# Ethernet_PHY_RJ45.net
KiCad netlist of a schematic drawn in Altium Designer
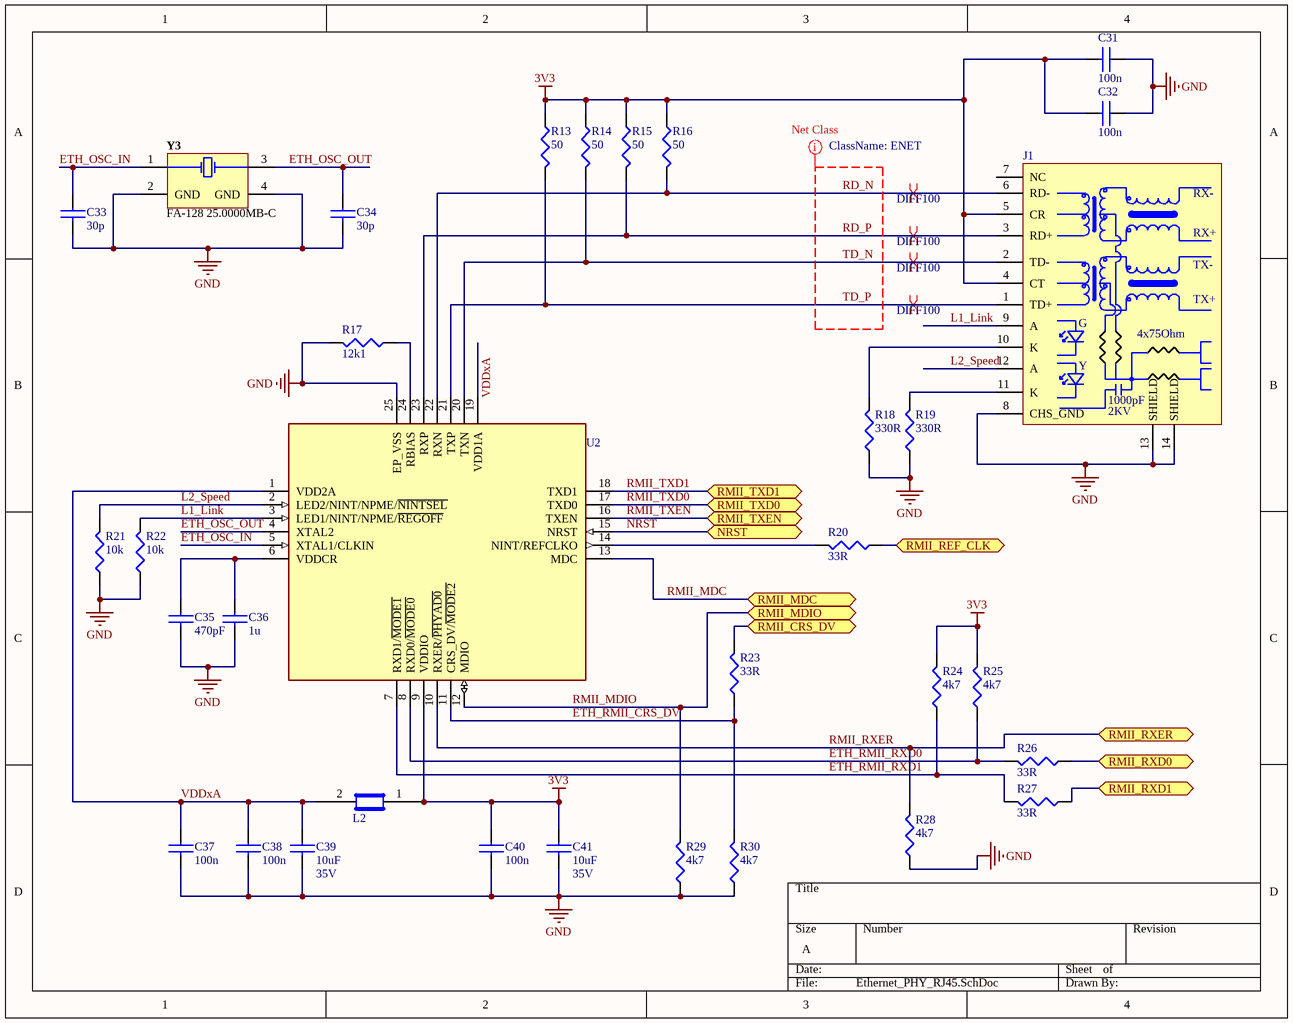
[diagram p0: Ethernet_PHY_RJ45.SchDoc]

(export (version "E")
  (design (tool "Eeschema 10.0.6"))
  (components
    (comp (ref "C31")
      (value "100n")
      (footprint "C0402")
      (description "CAP CER .10UF 50V X5R 10% 0402")
      (fields
        (field (name "MANUFACTURER") "TDK Corporation")
        (field (name "MANUFACTURER PART NUMBER") "C1005X5R1H104K")
      )
      (libsource (lib "iMX6_Rex_Development_Baseboard_V1I1") (part "C1005X5R1H104K"))
    )
    (comp (ref "C32")
      (value "100n")
      (footprint "C0402")
      (description "CAP CER .10UF 50V X5R 10% 0402")
      (fields
        (field (name "MANUFACTURER") "TDK Corporation")
        (field (name "MANUFACTURER PART NUMBER") "C1005X5R1H104K")
      )
      (libsource (lib "iMX6_Rex_Development_Baseboard_V1I1") (part "C1005X5R1H104K"))
    )
    (comp (ref "C33")
      (value "30p")
      (footprint "C0402")
      (description "CAP CER 18PF 50V C0G 5% 0402")
      (fields
        (field (name "MANUFACTURER") "TDK Corporation")
        (field (name "MANUFACTURER PART NUMBER") "C1005C0G1H180J")
      )
      (libsource (lib "iMX6_Rex_Development_Baseboard_V1I1") (part "C1005C0G1H180J"))
    )
    (comp (ref "C34")
      (value "30p")
      (footprint "C0402")
      (description "CAP CER 18PF 50V C0G 5% 0402")
      (fields
        (field (name "MANUFACTURER") "TDK Corporation")
        (field (name "MANUFACTURER PART NUMBER") "C1005C0G1H180J")
      )
      (libsource (lib "iMX6_Rex_Development_Baseboard_V1I1") (part "C1005C0G1H180J"))
    )
    (comp (ref "C35")
      (value "470pF")
      (footprint "C0402")
      (description "CAP CER 270PF 50V 10% X7R 0402")
      (fields
        (field (name "MANUFACTURER") "Murata Electronics North America")
        (field (name "MANUFACTURER PART NUMBER") "GRM155R71H271KA01D")
        (field (name ".CHECKED PCB") "RF")
        (field (name ".CHECKED SCH") "RF")
      )
      (libsource (lib "iMX6_Rex_Development_Baseboard_V1I1") (part "GRM155R71H271KA01D"))
    )
    (comp (ref "C36")
      (value "1u")
      (footprint "C0402")
      (description "CAP CER 1.0UF 16V X5R 0402")
      (fields
        (field (name "MANUFACTURER") "TDK Corporation")
        (field (name "MANUFACTURER PART NUMBER") "C1005X5R1C105K")
      )
      (libsource (lib "iMX6_Rex_Development_Baseboard_V1I1") (part "C1005X5R1C105K"))
    )
    (comp (ref "C37")
      (value "100n")
      (footprint "C0402")
      (description "CAP CER .10UF 50V X5R 10% 0402")
      (fields
        (field (name "MANUFACTURER") "TDK Corporation")
        (field (name "MANUFACTURER PART NUMBER") "C1005X5R1H104K")
      )
      (libsource (lib "iMX6_Rex_Development_Baseboard_V1I1") (part "C1005X5R1H104K"))
    )
    (comp (ref "C38")
      (value "100n")
      (footprint "C0402")
      (description "CAP CER .10UF 50V X5R 10% 0402")
      (fields
        (field (name "MANUFACTURER") "TDK Corporation")
        (field (name "MANUFACTURER PART NUMBER") "C1005X5R1H104K")
      )
      (libsource (lib "iMX6_Rex_Development_Baseboard_V1I1") (part "C1005X5R1H104K"))
    )
    (comp (ref "C39")
      (value "10uF")
      (footprint "C1206")
      (description "CAP CER 10UF 35V X5R 1206")
      (fields
        (field (name "MANUFACTURER") "Murata Electronics North America")
        (field (name "MANUFACTURER PART NUMBER") "GRM31CR6YA106KA12L")
        (field (name "VOLTAGE - RATED") "35V")
      )
      (libsource (lib "iMX6_Rex_Development_Baseboard_V1I1") (part "GRM31CR6YA106KA12L"))
    )
    (comp (ref "C40")
      (value "100n")
      (footprint "C0402")
      (description "CAP CER .10UF 50V X5R 10% 0402")
      (fields
        (field (name "MANUFACTURER") "TDK Corporation")
        (field (name "MANUFACTURER PART NUMBER") "C1005X5R1H104K")
      )
      (libsource (lib "iMX6_Rex_Development_Baseboard_V1I1") (part "C1005X5R1H104K"))
    )
    (comp (ref "C41")
      (value "10uF")
      (footprint "C1206")
      (description "CAP CER 10UF 35V X5R 1206")
      (fields
        (field (name "MANUFACTURER") "Murata Electronics North America")
        (field (name "MANUFACTURER PART NUMBER") "GRM31CR6YA106KA12L")
        (field (name "VOLTAGE - RATED") "35V")
      )
      (libsource (lib "iMX6_Rex_Development_Baseboard_V1I1") (part "GRM31CR6YA106KA12L"))
    )
    (comp (ref "J1")
      (value "RJ45")
      (footprint "RJ45_HAN_RUN")
      (description "DIP RJ45 Connector;")
      (fields (field (name "MANUFACTURER") "HanRun") (field (name "MANUFACTURER PART NUMBER") "HR911105A"))
      (libsource (lib "L1") (part "HR911105A"))
    )
    (comp (ref "L2")
      (value "MPZ1608S601A 600OHM/1A")
      (footprint "C0603")
      (description "FERRITE CHIP BEAD 600 OHM SMD 1A")
      (fields
        (field (name "MANUFACTURER") "TDK Corporation")
        (field (name "MANUFACTURER PART NUMBER") "MPZ1608S601A")
        (field (name ".CHECKED PCB") "RF")
        (field (name ".CHECKED SCH") "RF")
      )
      (libsource (lib "iMX6_Rex_Development_Baseboard_V1I1") (part "MPZ1608S601A"))
    )
    (comp (ref "R13")
      (value "50")
      (footprint "R0402")
      (description "RES 10.0K OHM 1/16W 1% 0402 SMD")
      (fields
        (field (name "MANUFACTURER") "Yageo")
        (field (name "MANUFACTURER PART NUMBER") "RC0402FR-0710KL")
      )
      (libsource (lib "iMX6_Rex_Development_Baseboard_V1I1") (part "RC0402FR-0710KL"))
    )
    (comp (ref "R14")
      (value "50")
      (footprint "R0402")
      (description "RES 10.0K OHM 1/16W 1% 0402 SMD")
      (fields
        (field (name "MANUFACTURER") "Yageo")
        (field (name "MANUFACTURER PART NUMBER") "RC0402FR-0710KL")
      )
      (libsource (lib "iMX6_Rex_Development_Baseboard_V1I1") (part "RC0402FR-0710KL"))
    )
    (comp (ref "R15")
      (value "50")
      (footprint "R0402")
      (description "RES 10.0K OHM 1/16W 1% 0402 SMD")
      (fields
        (field (name "MANUFACTURER") "Yageo")
        (field (name "MANUFACTURER PART NUMBER") "RC0402FR-0710KL")
      )
      (libsource (lib "iMX6_Rex_Development_Baseboard_V1I1") (part "RC0402FR-0710KL"))
    )
    (comp (ref "R16")
      (value "50")
      (footprint "R0402")
      (description "RES 10.0K OHM 1/16W 1% 0402 SMD")
      (fields
        (field (name "MANUFACTURER") "Yageo")
        (field (name "MANUFACTURER PART NUMBER") "RC0402FR-0710KL")
      )
      (libsource (lib "iMX6_Rex_Development_Baseboard_V1I1") (part "RC0402FR-0710KL"))
    )
    (comp (ref "R17")
      (value "12k1")
      (footprint "R0402")
      (description "RES 10.0K OHM 1/16W 1% 0402 SMD")
      (fields
        (field (name "MANUFACTURER") "Yageo")
        (field (name "MANUFACTURER PART NUMBER") "RC0402FR-0710KL")
      )
      (libsource (lib "iMX6_Rex_Development_Baseboard_V1I1") (part "RC0402FR-0710KL"))
    )
    (comp (ref "R18")
      (value "330R")
      (footprint "R0402")
      (description "RES 330 OHM 1/16W 1% 0402 SMD")
      (fields
        (field (name "MANUFACTURER") "Vishay Dale")
        (field (name "MANUFACTURER PART NUMBER") "CRCW0402330RFKED")
        (field (name ".CHECKED PCB") "RF")
        (field (name ".CHECKED SCH") "RF")
      )
      (libsource (lib "iMX6_Rex_Development_Baseboard_V1I1") (part "CRCW0402330RFKED"))
    )
    (comp (ref "R19")
      (value "330R")
      (footprint "R0402")
      (description "RES 330 OHM 1/16W 1% 0402 SMD")
      (fields
        (field (name "MANUFACTURER") "Vishay Dale")
        (field (name "MANUFACTURER PART NUMBER") "CRCW0402330RFKED")
        (field (name ".CHECKED PCB") "RF")
        (field (name ".CHECKED SCH") "RF")
      )
      (libsource (lib "iMX6_Rex_Development_Baseboard_V1I1") (part "CRCW0402330RFKED"))
    )
    (comp (ref "R20")
      (value "33R")
      (footprint "R0402")
      (description "RES 330 OHM 1/16W 1% 0402 SMD")
      (fields
        (field (name "MANUFACTURER") "Vishay Dale")
        (field (name "MANUFACTURER PART NUMBER") "CRCW0402330RFKED")
        (field (name ".CHECKED PCB") "RF")
        (field (name ".CHECKED SCH") "RF")
      )
      (libsource (lib "iMX6_Rex_Development_Baseboard_V1I1") (part "CRCW0402330RFKED"))
    )
    (comp (ref "R21")
      (value "10k")
      (footprint "R0402")
      (description "RES 10.0K OHM 1/16W 1% 0402 SMD")
      (fields
        (field (name "MANUFACTURER") "Yageo")
        (field (name "MANUFACTURER PART NUMBER") "RC0402FR-0710KL")
      )
      (libsource (lib "iMX6_Rex_Development_Baseboard_V1I1") (part "RC0402FR-0710KL"))
    )
    (comp (ref "R22")
      (value "10k")
      (footprint "R0402")
      (description "RES 10.0K OHM 1/16W 1% 0402 SMD")
      (fields
        (field (name "MANUFACTURER") "Yageo")
        (field (name "MANUFACTURER PART NUMBER") "RC0402FR-0710KL")
      )
      (libsource (lib "iMX6_Rex_Development_Baseboard_V1I1") (part "RC0402FR-0710KL"))
    )
    (comp (ref "R23")
      (value "33R")
      (footprint "R0402")
      (description "RES 330 OHM 1/16W 1% 0402 SMD")
      (fields
        (field (name "MANUFACTURER") "Vishay Dale")
        (field (name "MANUFACTURER PART NUMBER") "CRCW0402330RFKED")
        (field (name ".CHECKED PCB") "RF")
        (field (name ".CHECKED SCH") "RF")
      )
      (libsource (lib "iMX6_Rex_Development_Baseboard_V1I1") (part "CRCW0402330RFKED"))
    )
    (comp (ref "R24")
      (value "4k7")
      (footprint "R0402")
      (description "RES 10.0K OHM 1/16W 1% 0402 SMD")
      (fields
        (field (name "MANUFACTURER") "Yageo")
        (field (name "MANUFACTURER PART NUMBER") "RC0402FR-0710KL")
      )
      (libsource (lib "iMX6_Rex_Development_Baseboard_V1I1") (part "RC0402FR-0710KL"))
    )
    (comp (ref "R25")
      (value "4k7")
      (footprint "R0402")
      (description "RES 10.0K OHM 1/16W 1% 0402 SMD")
      (fields
        (field (name "MANUFACTURER") "Yageo")
        (field (name "MANUFACTURER PART NUMBER") "RC0402FR-0710KL")
      )
      (libsource (lib "iMX6_Rex_Development_Baseboard_V1I1") (part "RC0402FR-0710KL"))
    )
    (comp (ref "R26")
      (value "33R")
      (footprint "R0402")
      (description "RES 330 OHM 1/16W 1% 0402 SMD")
      (fields
        (field (name "MANUFACTURER") "Vishay Dale")
        (field (name "MANUFACTURER PART NUMBER") "CRCW0402330RFKED")
        (field (name ".CHECKED PCB") "RF")
        (field (name ".CHECKED SCH") "RF")
      )
      (libsource (lib "iMX6_Rex_Development_Baseboard_V1I1") (part "CRCW0402330RFKED"))
    )
    (comp (ref "R27")
      (value "33R")
      (footprint "R0402")
      (description "RES 330 OHM 1/16W 1% 0402 SMD")
      (fields
        (field (name "MANUFACTURER") "Vishay Dale")
        (field (name "MANUFACTURER PART NUMBER") "CRCW0402330RFKED")
        (field (name ".CHECKED PCB") "RF")
        (field (name ".CHECKED SCH") "RF")
      )
      (libsource (lib "iMX6_Rex_Development_Baseboard_V1I1") (part "CRCW0402330RFKED"))
    )
    (comp (ref "R28")
      (value "4k7")
      (footprint "R0402")
      (description "RES 10.0K OHM 1/16W 1% 0402 SMD")
      (fields
        (field (name "MANUFACTURER") "Yageo")
        (field (name "MANUFACTURER PART NUMBER") "RC0402FR-0710KL")
      )
      (libsource (lib "iMX6_Rex_Development_Baseboard_V1I1") (part "RC0402FR-0710KL"))
    )
    (comp (ref "R29")
      (value "4k7")
      (footprint "R0402")
      (description "RES 10.0K OHM 1/16W 1% 0402 SMD")
      (fields
        (field (name "MANUFACTURER") "Yageo")
        (field (name "MANUFACTURER PART NUMBER") "RC0402FR-0710KL")
      )
      (libsource (lib "iMX6_Rex_Development_Baseboard_V1I1") (part "RC0402FR-0710KL"))
    )
    (comp (ref "R30")
      (value "4k7")
      (footprint "R0402")
      (description "RES 10.0K OHM 1/16W 1% 0402 SMD")
      (fields
        (field (name "MANUFACTURER") "Yageo")
        (field (name "MANUFACTURER PART NUMBER") "RC0402FR-0710KL")
      )
      (libsource (lib "iMX6_Rex_Development_Baseboard_V1I1") (part "RC0402FR-0710KL"))
    )
    (comp (ref "U2")
      (value "LAN8742A-CZ-TR")
      (footprint "SamacSys:QFN50P400X400X100-25N-D")
      (description "Integrated Circuit")
      (fields (field (name "MOUSER PART NUMBER") "579-LAN8742A-CZ-TR"))
      (libsource (lib "*") (part "LAN8742A-CZ-TR"))
    )
    (comp (ref "Y3")
      (value "FA-128 25.0000MB-C")
      (footprint "EPSON-FA-128_V")
      (description "Range Crystal Unit, 25 MHz, -40 to 85 degC, 4-Pin SMD, RoHS, Tape and Reel")
      (libsource (lib "MiniPC") (part "CMP-1695-00001-3"))
    )
  )
  (nets
    (net (code "1") (name "/ETH_OSC_IN") (class "Default")
      (node (ref "C33") (pin "1") (pinfunction "1_1") (pintype "passive"))
      (node (ref "U2") (pin "5") (pinfunction "XTAL1/CLKIN_5") (pintype "input"))
      (node (ref "Y3") (pin "1") (pinfunction "X1_1") (pintype "passive"))
    )
    (net (code "2") (name "/ETH_OSC_OUT") (class "Default")
      (node (ref "C34") (pin "1") (pinfunction "1_1") (pintype "passive"))
      (node (ref "U2") (pin "4") (pinfunction "XTAL2_4") (pintype "passive"))
      (node (ref "Y3") (pin "3") (pinfunction "X2_3") (pintype "passive"))
    )
    (net (code "3") (name "/ETH_RMII_CRS_DV") (class "Default")
      (node (ref "R23") (pin "1") (pinfunction "1_1") (pintype "passive"))
      (node (ref "R30") (pin "2") (pinfunction "2_2") (pintype "passive"))
      (node (ref "U2") (pin "11") (pinfunction "CRS_DV/~{MODE2}_11") (pintype "passive"))
    )
    (net (code "4") (name "/ETH_RMII_RXD0") (class "Default")
      (node (ref "R25") (pin "1") (pinfunction "1_1") (pintype "passive"))
      (node (ref "R26") (pin "2") (pinfunction "2_2") (pintype "passive"))
      (node (ref "U2") (pin "8") (pinfunction "RXD0/~{MODE0}_8") (pintype "passive"))
    )
    (net (code "5") (name "/ETH_RMII_RXD1") (class "Default")
      (node (ref "R24") (pin "1") (pinfunction "1_1") (pintype "passive"))
      (node (ref "R27") (pin "2") (pinfunction "2_2") (pintype "passive"))
      (node (ref "U2") (pin "7") (pinfunction "RXD1/~{MODE1}_7") (pintype "passive"))
    )
    (net (code "6") (name "/L1_Link") (class "Default")
      (node (ref "J1") (pin "9") (pinfunction "A_9") (pintype "power_in"))
      (node (ref "R22") (pin "2") (pinfunction "2_2") (pintype "passive"))
      (node (ref "U2") (pin "3") (pinfunction "LED1/NINT/NPME/~{REGOFF}_3") (pintype "input"))
    )
    (net (code "7") (name "/L2_Speed") (class "Default")
      (node (ref "J1") (pin "12") (pinfunction "A_12") (pintype "power_in"))
      (node (ref "R21") (pin "2") (pinfunction "2_2") (pintype "passive"))
      (node (ref "U2") (pin "2") (pinfunction "LED2/NINT/NPME/~{NINTSEL}_2") (pintype "input"))
    )
    (net (code "8") (name "/NRST") (class "Default")
      (node (ref "U2") (pin "15") (pinfunction "NRST_15") (pintype "input"))
    )
    (net (code "9") (name "/RD_N") (class "Default")
      (node (ref "J1") (pin "6") (pinfunction "RD-_6") (pintype "power_in"))
      (node (ref "R16") (pin "2") (pinfunction "2_2") (pintype "passive"))
      (node (ref "U2") (pin "22") (pinfunction "RXN_22") (pintype "passive"))
    )
    (net (code "10") (name "/RD_P") (class "Default")
      (node (ref "J1") (pin "3") (pinfunction "RD+_3") (pintype "power_in"))
      (node (ref "R15") (pin "2") (pinfunction "2_2") (pintype "passive"))
      (node (ref "U2") (pin "23") (pinfunction "RXP_23") (pintype "passive"))
    )
    (net (code "11") (name "/RMII_CRS_DV") (class "Default")
      (node (ref "R23") (pin "2") (pinfunction "2_2") (pintype "passive"))
    )
    (net (code "12") (name "/RMII_MDC") (class "Default")
      (node (ref "U2") (pin "13") (pinfunction "MDC_13") (pintype "passive"))
    )
    (net (code "13") (name "/RMII_MDIO") (class "Default")
      (node (ref "R29") (pin "2") (pinfunction "2_2") (pintype "passive"))
      (node (ref "U2") (pin "12") (pinfunction "MDIO_12") (pintype "bidirectional"))
    )
    (net (code "14") (name "/RMII_REF_CLK") (class "Default")
      (node (ref "R20") (pin "1") (pinfunction "1_1") (pintype "passive"))
    )
    (net (code "15") (name "/RMII_RXD0") (class "Default")
      (node (ref "R26") (pin "1") (pinfunction "1_1") (pintype "passive"))
    )
    (net (code "16") (name "/RMII_RXD1") (class "Default")
      (node (ref "R27") (pin "1") (pinfunction "1_1") (pintype "passive"))
    )
    (net (code "17") (name "/RMII_RXER") (class "Default")
      (node (ref "R28") (pin "2") (pinfunction "2_2") (pintype "passive"))
      (node (ref "U2") (pin "10") (pinfunction "RXER/~{PHYAD0}_10") (pintype "passive"))
    )
    (net (code "18") (name "/RMII_TXD0") (class "Default")
      (node (ref "U2") (pin "17") (pinfunction "TXD0_17") (pintype "passive"))
    )
    (net (code "19") (name "/RMII_TXD1") (class "Default")
      (node (ref "U2") (pin "18") (pinfunction "TXD1_18") (pintype "passive"))
    )
    (net (code "20") (name "/RMII_TXEN") (class "Default")
      (node (ref "U2") (pin "16") (pinfunction "TXEN_16") (pintype "passive"))
    )
    (net (code "21") (name "/TD_N") (class "Default")
      (node (ref "J1") (pin "2") (pinfunction "TD-_2") (pintype "power_in"))
      (node (ref "R14") (pin "2") (pinfunction "2_2") (pintype "passive"))
      (node (ref "U2") (pin "20") (pinfunction "TXN_20") (pintype "passive"))
    )
    (net (code "22") (name "/TD_P") (class "Default")
      (node (ref "J1") (pin "1") (pinfunction "TD+_1") (pintype "power_in"))
      (node (ref "R13") (pin "2") (pinfunction "2_2") (pintype "passive"))
      (node (ref "U2") (pin "21") (pinfunction "TXP_21") (pintype "passive"))
    )
    (net (code "23") (name "/VDDxA") (class "Default")
      (node (ref "C37") (pin "1") (pinfunction "1_1") (pintype "passive"))
      (node (ref "C38") (pin "1") (pinfunction "1_1") (pintype "passive"))
      (node (ref "C39") (pin "1") (pinfunction "1_1") (pintype "passive"))
      (node (ref "L2") (pin "2") (pinfunction "2_2") (pintype "passive"))
      (node (ref "U2") (pin "1") (pinfunction "VDD2A_1") (pintype "power_in"))
      (node (ref "U2") (pin "19") (pinfunction "VDD1A_19") (pintype "power_in"))
    )
    (net (code "24") (name "3V3") (class "Default")
      (node (ref "C31") (pin "2") (pinfunction "2_2") (pintype "passive"))
      (node (ref "C32") (pin "2") (pinfunction "2_2") (pintype "passive"))
      (node (ref "C40") (pin "1") (pinfunction "1_1") (pintype "passive"))
      (node (ref "C41") (pin "1") (pinfunction "1_1") (pintype "passive"))
      (node (ref "J1") (pin "4") (pinfunction "CT_4") (pintype "power_in"))
      (node (ref "J1") (pin "5") (pinfunction "CR_5") (pintype "power_in"))
      (node (ref "L2") (pin "1") (pinfunction "1_1") (pintype "passive"))
      (node (ref "R13") (pin "1") (pinfunction "1_1") (pintype "passive"))
      (node (ref "R14") (pin "1") (pinfunction "1_1") (pintype "passive"))
      (node (ref "R15") (pin "1") (pinfunction "1_1") (pintype "passive"))
      (node (ref "R16") (pin "1") (pinfunction "1_1") (pintype "passive"))
      (node (ref "R24") (pin "2") (pinfunction "2_2") (pintype "passive"))
      (node (ref "R25") (pin "2") (pinfunction "2_2") (pintype "passive"))
      (node (ref "U2") (pin "9") (pinfunction "VDDIO_9") (pintype "power_in"))
    )
    (net (code "25") (name "GND") (class "Default")
      (node (ref "C31") (pin "1") (pinfunction "1_1") (pintype "passive"))
      (node (ref "C32") (pin "1") (pinfunction "1_1") (pintype "passive"))
      (node (ref "C33") (pin "2") (pinfunction "2_2") (pintype "passive"))
      (node (ref "C34") (pin "2") (pinfunction "2_2") (pintype "passive"))
      (node (ref "C35") (pin "2") (pinfunction "2_2") (pintype "passive"))
      (node (ref "C36") (pin "2") (pinfunction "2_2") (pintype "passive"))
      (node (ref "C37") (pin "2") (pinfunction "2_2") (pintype "passive"))
      (node (ref "C38") (pin "2") (pinfunction "2_2") (pintype "passive"))
      (node (ref "C39") (pin "2") (pinfunction "2_2") (pintype "passive"))
      (node (ref "C40") (pin "2") (pinfunction "2_2") (pintype "passive"))
      (node (ref "C41") (pin "2") (pinfunction "2_2") (pintype "passive"))
      (node (ref "J1") (pin "13") (pinfunction "SHIELD_13") (pintype "power_in"))
      (node (ref "J1") (pin "14") (pinfunction "SHIELD_14") (pintype "power_in"))
      (node (ref "J1") (pin "8") (pinfunction "CHS_GND_8") (pintype "power_in"))
      (node (ref "R17") (pin "2") (pinfunction "2_2") (pintype "passive"))
      (node (ref "R18") (pin "1") (pinfunction "1_1") (pintype "passive"))
      (node (ref "R19") (pin "1") (pinfunction "1_1") (pintype "passive"))
      (node (ref "R21") (pin "1") (pinfunction "1_1") (pintype "passive"))
      (node (ref "R22") (pin "1") (pinfunction "1_1") (pintype "passive"))
      (node (ref "R28") (pin "1") (pinfunction "1_1") (pintype "passive"))
      (node (ref "R29") (pin "1") (pinfunction "1_1") (pintype "passive"))
      (node (ref "R30") (pin "1") (pinfunction "1_1") (pintype "passive"))
      (node (ref "U2") (pin "25") (pinfunction "EP_VSS_25") (pintype "power_in"))
      (node (ref "Y3") (pin "2") (pinfunction "GND_2") (pintype "power_in"))
      (node (ref "Y3") (pin "4") (pinfunction "GND_4") (pintype "power_in"))
    )
    (net (code "26") (name "Net-(J1-K-Pad10)") (class "Default")
      (node (ref "J1") (pin "10") (pinfunction "K_10") (pintype "power_in"))
      (node (ref "R18") (pin "2") (pinfunction "2_2") (pintype "passive"))
    )
    (net (code "27") (name "Net-(J1-K-Pad11)") (class "Default")
      (node (ref "J1") (pin "11") (pinfunction "K_11") (pintype "power_in"))
      (node (ref "R19") (pin "2") (pinfunction "2_2") (pintype "passive"))
    )
    (net (code "28") (name "Net-(U2-NINT{slash}REFCLKO)") (class "Default")
      (node (ref "R20") (pin "2") (pinfunction "2_2") (pintype "passive"))
      (node (ref "U2") (pin "14") (pinfunction "NINT/REFCLKO_14") (pintype "output"))
    )
    (net (code "29") (name "Net-(U2-RBIAS)") (class "Default")
      (node (ref "R17") (pin "1") (pinfunction "1_1") (pintype "passive"))
      (node (ref "U2") (pin "24") (pinfunction "RBIAS_24") (pintype "passive"))
    )
    (net (code "30") (name "Net-(U2-VDDCR)") (class "Default")
      (node (ref "C35") (pin "1") (pinfunction "1_1") (pintype "passive"))
      (node (ref "C36") (pin "1") (pinfunction "1_1") (pintype "passive"))
      (node (ref "U2") (pin "6") (pinfunction "VDDCR_6") (pintype "power_in"))
    )
    (net (code "31") (name "unconnected-(J1-NC-Pad7)") (class "Default")
      (node (ref "J1") (pin "7") (pinfunction "NC_7") (pintype "power_in"))
    )
  )
)
